# v3_Painting_Machine_Schematic.net
KiCad netlist of a schematic drawn in EAGLE
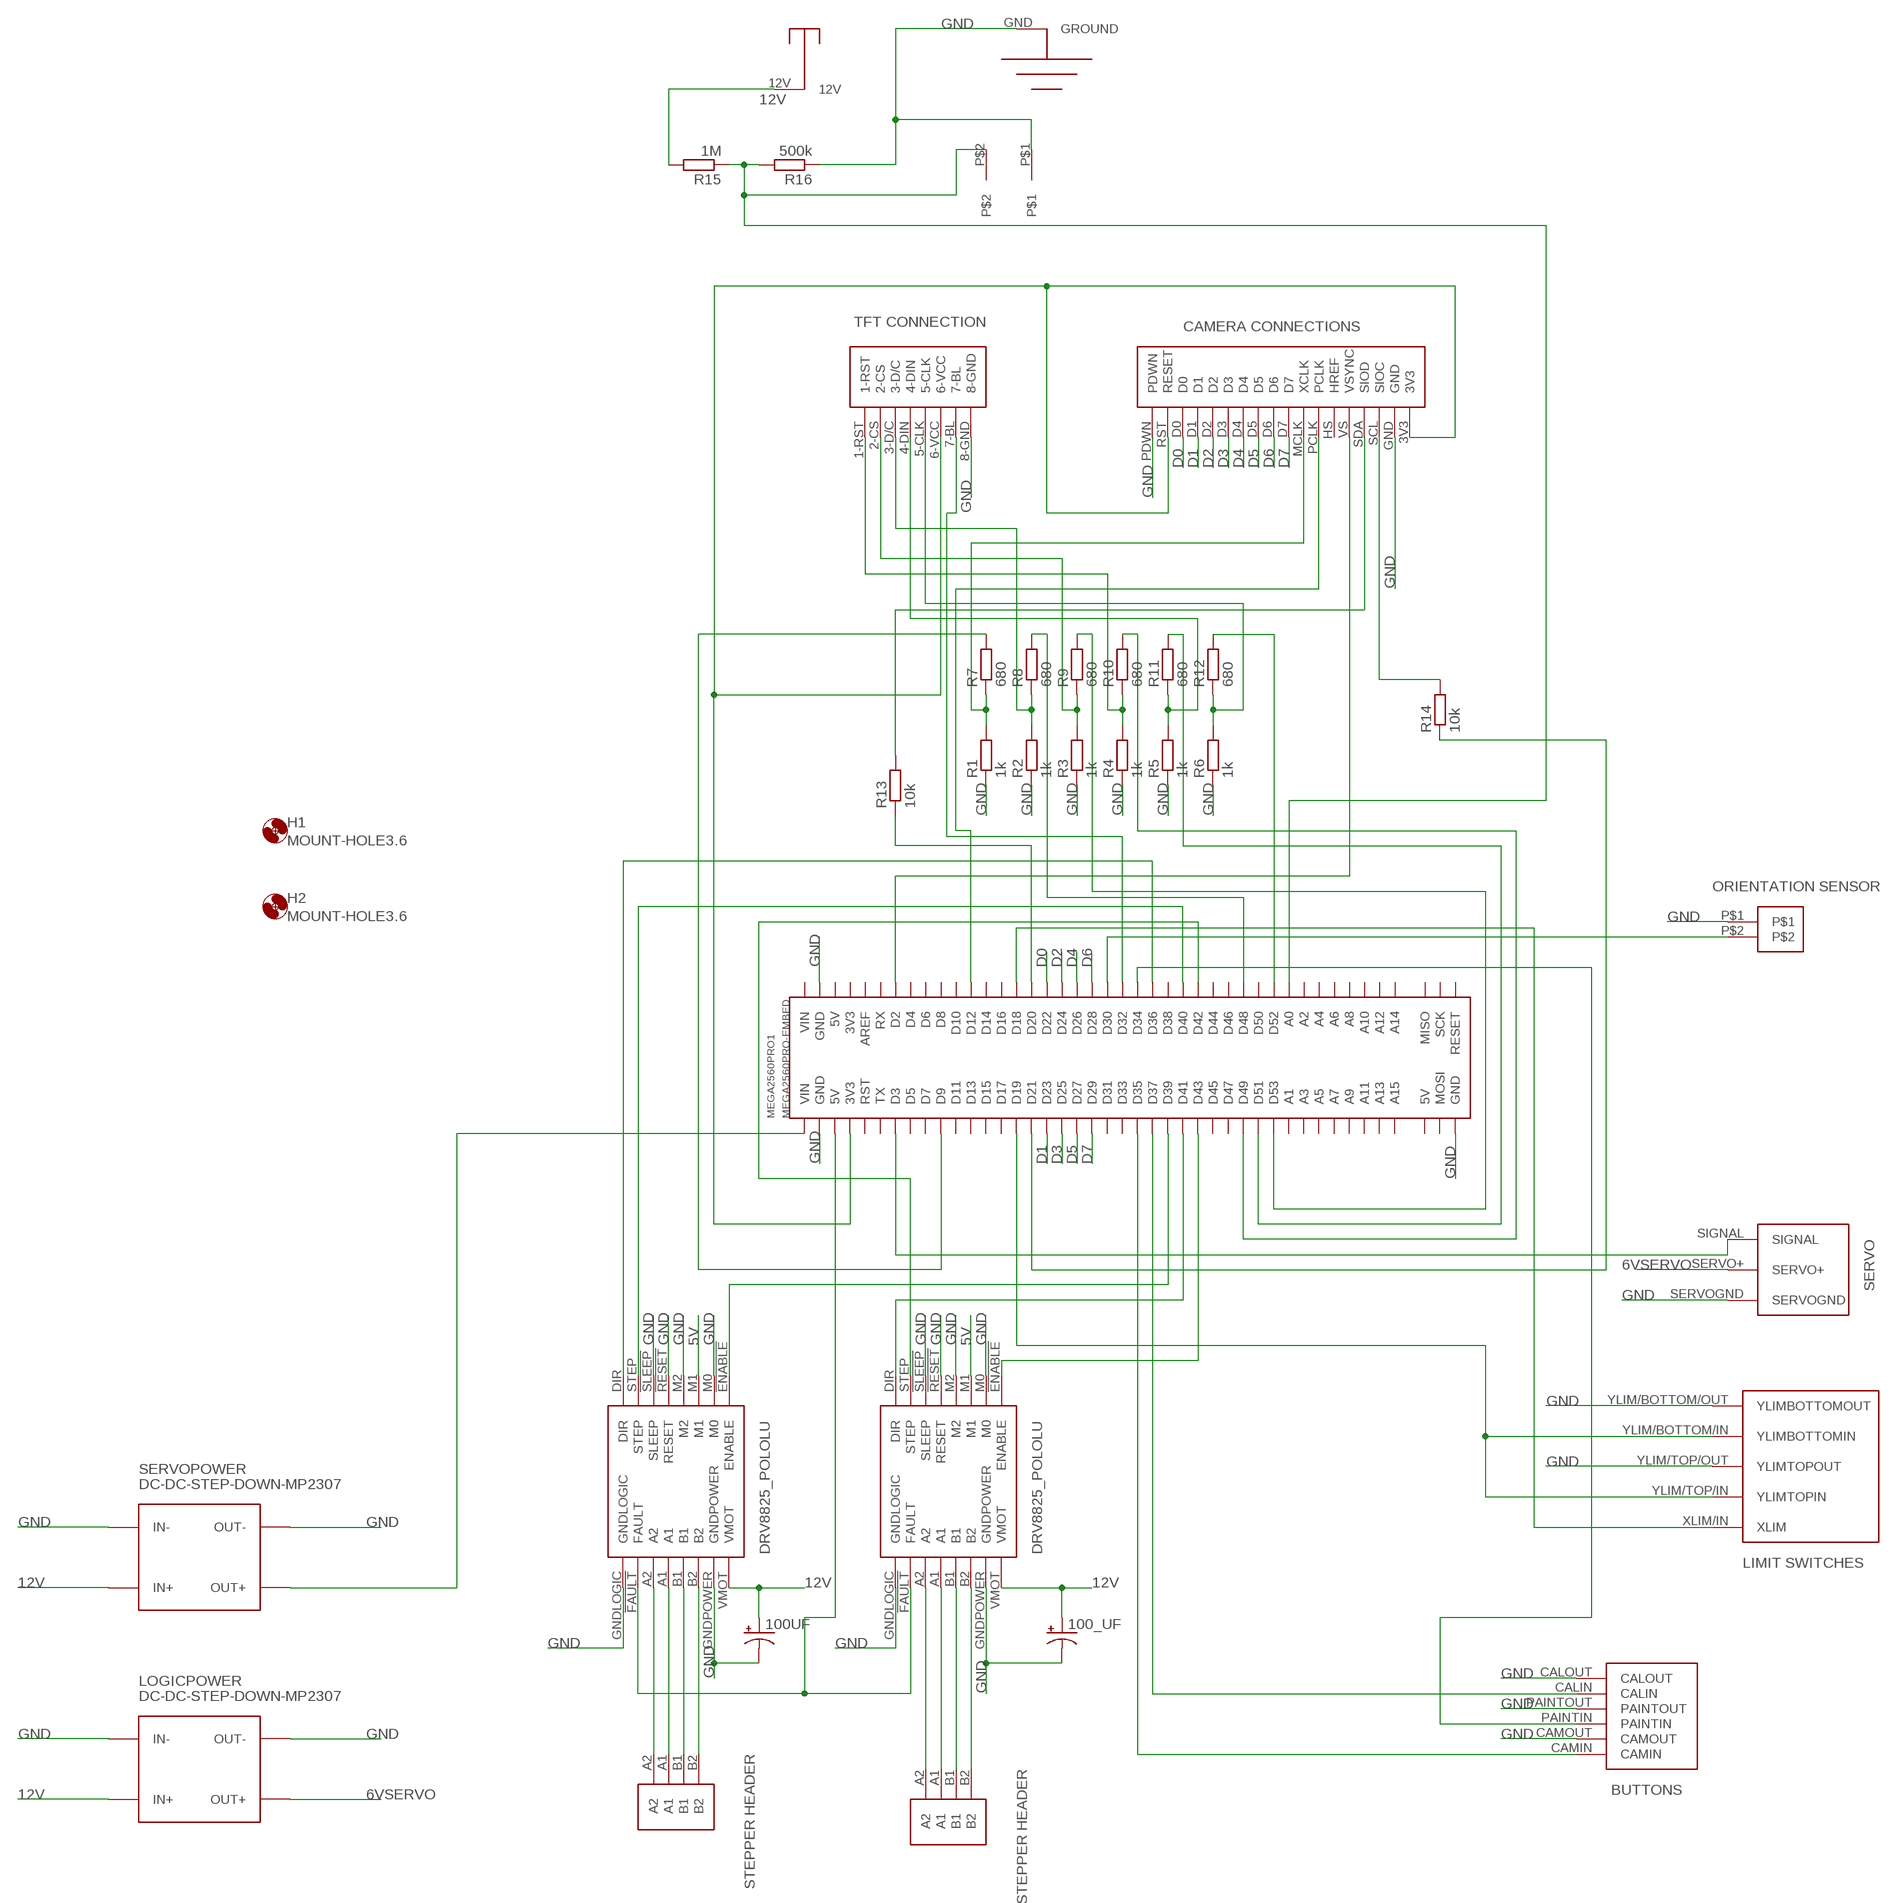
[diagram p0: schematic, sheet 1]

(export (version "E")
  (design (tool "Eeschema 10.0.6"))
  (components
    (comp (ref "100UF")
      (value "CPOL-USB45181B")
      (footprint "eagle-import:B45181B")
      (libsource (lib "eagle-import") (part "CPOL-USB45181B"))
    )
    (comp (ref "100_UF")
      (value "CPOL-USB45181B")
      (footprint "eagle-import:B45181B")
      (libsource (lib "eagle-import") (part "CPOL-USB45181B"))
    )
    (comp (ref "H1")
      (value "MOUNT-HOLE3.6")
      (footprint "eagle-import:3,6")
      (libsource (lib "eagle-import") (part "MOUNT-HOLE3.6"))
    )
    (comp (ref "H2")
      (value "MOUNT-HOLE3.6")
      (footprint "eagle-import:3,6")
      (libsource (lib "eagle-import") (part "MOUNT-HOLE3.6"))
    )
    (comp (ref "LOGICPOWER")
      (value "DC-DC-STEP-DOWN-MP2307")
      (footprint "eagle-import:DC-DC-STEP-DOWN-MP2307")
      (libsource (lib "eagle-import") (part "DC-DC-STEP-DOWN-MP2307"))
    )
    (comp (ref "MEGA2560PRO1")
      (value "MEGA2560PRO-EMBED")
      (footprint "eagle-import:MEGA2560PRO-EMBED")
      (libsource (lib "eagle-import") (part "MEGA2560PRO-EMBED"))
    )
    (comp (ref "R1")
      (value "1k")
      (footprint "eagle-import:0207_7")
      (libsource (lib "eagle-import") (part "R-EU_0207/7"))
    )
    (comp (ref "R2")
      (value "1k")
      (footprint "eagle-import:0207_7")
      (libsource (lib "eagle-import") (part "R-EU_0207/7"))
    )
    (comp (ref "R3")
      (value "1k")
      (footprint "eagle-import:0207_7")
      (libsource (lib "eagle-import") (part "R-EU_0207/7"))
    )
    (comp (ref "R4")
      (value "1k")
      (footprint "eagle-import:0207_7")
      (libsource (lib "eagle-import") (part "R-EU_0207/7"))
    )
    (comp (ref "R5")
      (value "1k")
      (footprint "eagle-import:0207_7")
      (libsource (lib "eagle-import") (part "R-EU_0207/7"))
    )
    (comp (ref "R6")
      (value "1k")
      (footprint "eagle-import:0207_7")
      (libsource (lib "eagle-import") (part "R-EU_0207/7"))
    )
    (comp (ref "R7")
      (value "680")
      (footprint "eagle-import:0207_7")
      (libsource (lib "eagle-import") (part "R-EU_0207/7"))
    )
    (comp (ref "R8")
      (value "680")
      (footprint "eagle-import:0207_7")
      (libsource (lib "eagle-import") (part "R-EU_0207/7"))
    )
    (comp (ref "R9")
      (value "680")
      (footprint "eagle-import:0207_7")
      (libsource (lib "eagle-import") (part "R-EU_0207/7"))
    )
    (comp (ref "R10")
      (value "680")
      (footprint "eagle-import:0207_7")
      (libsource (lib "eagle-import") (part "R-EU_0207/7"))
    )
    (comp (ref "R11")
      (value "680")
      (footprint "eagle-import:0207_7")
      (libsource (lib "eagle-import") (part "R-EU_0207/7"))
    )
    (comp (ref "R12")
      (value "680")
      (footprint "eagle-import:0207_7")
      (libsource (lib "eagle-import") (part "R-EU_0207/7"))
    )
    (comp (ref "R13")
      (value "10k")
      (footprint "eagle-import:0207_7")
      (libsource (lib "eagle-import") (part "R-EU_0207/7"))
    )
    (comp (ref "R14")
      (value "10k")
      (footprint "eagle-import:0207_7")
      (libsource (lib "eagle-import") (part "R-EU_0207/7"))
    )
    (comp (ref "R15")
      (value "1M")
      (footprint "eagle-import:0207_7")
      (libsource (lib "eagle-import") (part "R-EU_0207/7"))
    )
    (comp (ref "R16")
      (value "500k")
      (footprint "eagle-import:0207_7")
      (libsource (lib "eagle-import") (part "R-EU_0207/7"))
    )
    (comp (ref "SERVOPOWER")
      (value "DC-DC-STEP-DOWN-MP2307")
      (footprint "eagle-import:DC-DC-STEP-DOWN-MP2307")
      (libsource (lib "eagle-import") (part "DC-DC-STEP-DOWN-MP2307"))
    )
    (comp (ref "U$1")
      (value "DRV8825_POLOLU_CARRIER")
      (footprint "eagle-import:DRV8825_POLOLU")
      (libsource (lib "eagle-import") (part "DRV8825_POLOLU_CARRIER"))
    )
    (comp (ref "U$2")
      (value "DRV8825_POLOLU_CARRIER")
      (footprint "eagle-import:DRV8825_POLOLU")
      (libsource (lib "eagle-import") (part "DRV8825_POLOLU_CARRIER"))
    )
    (comp (ref "U$4")
      (value "TFT/CONNECTIONS")
      (footprint "eagle-import:TFTCONNECTIONS")
      (libsource (lib "eagle-import") (part "TFT/CONNECTIONS"))
    )
    (comp (ref "U$5")
      (value "OV7670CONNECTIONS")
      (footprint "eagle-import:CAMERACONNECTIONS")
      (libsource (lib "eagle-import") (part "OV7670CONNECTIONS"))
    )
    (comp (ref "U$6")
      (value "ORIENTATIONSENSOR")
      (footprint "eagle-import:ORIENTATIONSENSOR")
      (libsource (lib "eagle-import") (part "ORIENTATIONSENSOR"))
    )
    (comp (ref "U$7")
      (value "12V")
      (footprint "eagle-import:VCC")
      (libsource (lib "eagle-import") (part "12V"))
    )
    (comp (ref "U$8")
      (value "GROUND")
      (footprint "eagle-import:GROUND")
      (libsource (lib "eagle-import") (part "GROUND"))
    )
    (comp (ref "U$9")
      (value "STEPPER_HEADER")
      (footprint "eagle-import:STEPPER_HEADER")
      (libsource (lib "eagle-import") (part "STEPPER_HEADER"))
    )
    (comp (ref "U$10")
      (value "STEPPER_HEADER")
      (footprint "eagle-import:STEPPER_HEADER")
      (libsource (lib "eagle-import") (part "STEPPER_HEADER"))
    )
    (comp (ref "U$11")
      (value "SERVO")
      (footprint "eagle-import:SERVO")
      (libsource (lib "eagle-import") (part "SERVO"))
    )
    (comp (ref "U$12")
      (value "LIMITSWITCHES")
      (footprint "eagle-import:LIMITSWITCHES")
      (libsource (lib "eagle-import") (part "LIMITSWITCHES"))
    )
    (comp (ref "U$13")
      (value "BUTTONS")
      (footprint "eagle-import:INPUTBUTTONS")
      (libsource (lib "eagle-import") (part "BUTTONS"))
    )
    (comp (ref "U$14")
      (value "CERAMICCAPACITOR")
      (footprint "eagle-import:CERAMICCAPACITOR")
      (libsource (lib "eagle-import") (part "CERAMICCAPACITOR"))
    )
  )
  (nets
    (net (code "1") (name "/5V") (class "Default")
      (node (ref "U$1") (pin "M1") (pinfunction "M1_M1") (pintype "bidirectional"))
      (node (ref "U$2") (pin "M1") (pinfunction "M1_M1") (pintype "bidirectional"))
    )
    (net (code "2") (name "/6VSERVO") (class "Default")
      (node (ref "LOGICPOWER") (pin "OUT+") (pinfunction "OUT+_OUT+") (pintype "bidirectional"))
      (node (ref "U$11") (pin "SERVO+") (pinfunction "SERVO+_SERVO+") (pintype "bidirectional"))
    )
    (net (code "3") (name "/12V") (class "Default")
      (node (ref "100UF") (pin "+") (pinfunction "+_+") (pintype "passive"))
      (node (ref "100_UF") (pin "+") (pinfunction "+_+") (pintype "passive"))
      (node (ref "LOGICPOWER") (pin "IN+") (pinfunction "IN+_IN+") (pintype "bidirectional"))
      (node (ref "R15") (pin "2") (pinfunction "2_2") (pintype "passive"))
      (node (ref "SERVOPOWER") (pin "IN+") (pinfunction "IN+_IN+") (pintype "bidirectional"))
      (node (ref "U$1") (pin "VMOT") (pinfunction "VMOT_VMOT") (pintype "bidirectional"))
      (node (ref "U$2") (pin "VMOT") (pinfunction "VMOT_VMOT") (pintype "bidirectional"))
      (node (ref "U$7") (pin "12V") (pinfunction "12V_12V") (pintype "bidirectional"))
    )
    (net (code "4") (name "/D0") (class "Default")
      (node (ref "MEGA2560PRO1") (pin "D22") (pinfunction "D22_D22") (pintype "bidirectional"))
      (node (ref "U$5") (pin "D0") (pinfunction "D0_D0") (pintype "bidirectional"))
    )
    (net (code "5") (name "/D1") (class "Default")
      (node (ref "MEGA2560PRO1") (pin "D23") (pinfunction "D23_D23") (pintype "bidirectional"))
      (node (ref "U$5") (pin "D1") (pinfunction "D1_D1") (pintype "bidirectional"))
    )
    (net (code "6") (name "/D2") (class "Default")
      (node (ref "MEGA2560PRO1") (pin "D24") (pinfunction "D24_D24") (pintype "bidirectional"))
      (node (ref "U$5") (pin "D2") (pinfunction "D2_D2") (pintype "bidirectional"))
    )
    (net (code "7") (name "/D3") (class "Default")
      (node (ref "MEGA2560PRO1") (pin "D25") (pinfunction "D25_D25") (pintype "bidirectional"))
      (node (ref "U$5") (pin "D3") (pinfunction "D3_D3") (pintype "bidirectional"))
    )
    (net (code "8") (name "/D4") (class "Default")
      (node (ref "MEGA2560PRO1") (pin "D26") (pinfunction "D26_D26") (pintype "bidirectional"))
      (node (ref "U$5") (pin "D4") (pinfunction "D4_D4") (pintype "bidirectional"))
    )
    (net (code "9") (name "/D5") (class "Default")
      (node (ref "MEGA2560PRO1") (pin "D27") (pinfunction "D27_D27") (pintype "bidirectional"))
      (node (ref "U$5") (pin "D5") (pinfunction "D5_D5") (pintype "bidirectional"))
    )
    (net (code "10") (name "/D6") (class "Default")
      (node (ref "MEGA2560PRO1") (pin "D28") (pinfunction "D28_D28") (pintype "bidirectional"))
      (node (ref "U$5") (pin "D6") (pinfunction "D6_D6") (pintype "bidirectional"))
    )
    (net (code "11") (name "/D7") (class "Default")
      (node (ref "MEGA2560PRO1") (pin "D29") (pinfunction "D29_D29") (pintype "bidirectional"))
      (node (ref "U$5") (pin "D7") (pinfunction "D7_D7") (pintype "bidirectional"))
    )
    (net (code "12") (name "/GND") (class "Default")
      (node (ref "100UF") (pin "-") (pinfunction "-_-") (pintype "passive"))
      (node (ref "100_UF") (pin "-") (pinfunction "-_-") (pintype "passive"))
      (node (ref "LOGICPOWER") (pin "IN-") (pinfunction "IN-_IN-") (pintype "bidirectional"))
      (node (ref "LOGICPOWER") (pin "OUT-") (pinfunction "OUT-_OUT-") (pintype "bidirectional"))
      (node (ref "MEGA2560PRO1") (pin "GND@1") (pinfunction "GND_GND@1") (pintype "bidirectional"))
      (node (ref "MEGA2560PRO1") (pin "GND@2") (pinfunction "GND_GND@2") (pintype "bidirectional"))
      (node (ref "MEGA2560PRO1") (pin "GND@3") (pinfunction "GND_GND@3") (pintype "bidirectional"))
      (node (ref "R1") (pin "1") (pinfunction "1_1") (pintype "passive"))
      (node (ref "R16") (pin "1") (pinfunction "1_1") (pintype "passive"))
      (node (ref "R2") (pin "1") (pinfunction "1_1") (pintype "passive"))
      (node (ref "R3") (pin "1") (pinfunction "1_1") (pintype "passive"))
      (node (ref "R4") (pin "1") (pinfunction "1_1") (pintype "passive"))
      (node (ref "R5") (pin "1") (pinfunction "1_1") (pintype "passive"))
      (node (ref "R6") (pin "1") (pinfunction "1_1") (pintype "passive"))
      (node (ref "SERVOPOWER") (pin "IN-") (pinfunction "IN-_IN-") (pintype "bidirectional"))
      (node (ref "SERVOPOWER") (pin "OUT-") (pinfunction "OUT-_OUT-") (pintype "bidirectional"))
      (node (ref "U$1") (pin "!RESET") (pinfunction "RESET_!RESET") (pintype "bidirectional"))
      (node (ref "U$1") (pin "!SLEEP") (pinfunction "SLEEP_!SLEEP") (pintype "bidirectional"))
      (node (ref "U$1") (pin "GNDLOGIC") (pinfunction "GNDLOGIC_GNDLOGIC") (pintype "bidirectional"))
      (node (ref "U$1") (pin "GNDPOWER") (pinfunction "GNDPOWER_GNDPOWER") (pintype "bidirectional"))
      (node (ref "U$1") (pin "M0") (pinfunction "M0_M0") (pintype "bidirectional"))
      (node (ref "U$1") (pin "M2") (pinfunction "M2_M2") (pintype "bidirectional"))
      (node (ref "U$11") (pin "SERVOGND") (pinfunction "SERVOGND_SERVOGND") (pintype "bidirectional"))
      (node (ref "U$12") (pin "YLIM/BOTTOM/OUT") (pinfunction "YLIMBOTTOMOUT_YLIM/BOTTOM/OUT") (pintype "bidirectional"))
      (node (ref "U$12") (pin "YLIM/TOP/OUT") (pinfunction "YLIMTOPOUT_YLIM/TOP/OUT") (pintype "bidirectional"))
      (node (ref "U$13") (pin "CALOUT") (pinfunction "CALOUT_CALOUT") (pintype "bidirectional"))
      (node (ref "U$13") (pin "CAMOUT") (pinfunction "CAMOUT_CAMOUT") (pintype "bidirectional"))
      (node (ref "U$13") (pin "PAINTOUT") (pinfunction "PAINTOUT_PAINTOUT") (pintype "bidirectional"))
      (node (ref "U$14") (pin "P$1") (pinfunction "P$1_P$1") (pintype "bidirectional"))
      (node (ref "U$2") (pin "!RESET") (pinfunction "RESET_!RESET") (pintype "bidirectional"))
      (node (ref "U$2") (pin "!SLEEP") (pinfunction "SLEEP_!SLEEP") (pintype "bidirectional"))
      (node (ref "U$2") (pin "GNDLOGIC") (pinfunction "GNDLOGIC_GNDLOGIC") (pintype "bidirectional"))
      (node (ref "U$2") (pin "GNDPOWER") (pinfunction "GNDPOWER_GNDPOWER") (pintype "bidirectional"))
      (node (ref "U$2") (pin "M0") (pinfunction "M0_M0") (pintype "bidirectional"))
      (node (ref "U$2") (pin "M2") (pinfunction "M2_M2") (pintype "bidirectional"))
      (node (ref "U$4") (pin "8-GND") (pinfunction "8-GND_8-GND") (pintype "bidirectional"))
      (node (ref "U$5") (pin "GND") (pinfunction "GND_GND") (pintype "bidirectional"))
      (node (ref "U$5") (pin "PDWN") (pinfunction "PDWN_PDWN") (pintype "bidirectional"))
      (node (ref "U$6") (pin "P$1") (pinfunction "P$1_P$1") (pintype "bidirectional"))
      (node (ref "U$8") (pin "GND") (pinfunction "GROUND_GND") (pintype "bidirectional"))
    )
    (net (code "13") (name "Net-(MEGA2560PRO1-PadA0)") (class "Default")
      (node (ref "MEGA2560PRO1") (pin "A0") (pinfunction "A0_A0") (pintype "bidirectional"))
      (node (ref "R15") (pin "1") (pinfunction "1_1") (pintype "passive"))
      (node (ref "R16") (pin "2") (pinfunction "2_2") (pintype "passive"))
      (node (ref "U$14") (pin "P$2") (pinfunction "P$2_P$2") (pintype "bidirectional"))
    )
    (net (code "14") (name "Net-(MEGA2560PRO1-PadD3)") (class "Default")
      (node (ref "MEGA2560PRO1") (pin "D3") (pinfunction "D3_D3") (pintype "bidirectional"))
      (node (ref "U$11") (pin "SIGNAL") (pinfunction "SIGNAL_SIGNAL") (pintype "bidirectional"))
    )
    (net (code "15") (name "Net-(MEGA2560PRO1-PadD9)") (class "Default")
      (node (ref "MEGA2560PRO1") (pin "D9") (pinfunction "D9_D9") (pintype "bidirectional"))
      (node (ref "R7") (pin "2") (pinfunction "2_2") (pintype "passive"))
    )
    (net (code "16") (name "Net-(MEGA2560PRO1-PadD12)") (class "Default")
      (node (ref "MEGA2560PRO1") (pin "D12") (pinfunction "D12_D12") (pintype "bidirectional"))
      (node (ref "U$5") (pin "PCLK") (pinfunction "PCLK_PCLK") (pintype "bidirectional"))
    )
    (net (code "17") (name "Net-(MEGA2560PRO1-PadD20)") (class "Default")
      (node (ref "MEGA2560PRO1") (pin "D20") (pinfunction "D20_D20") (pintype "bidirectional"))
      (node (ref "R13") (pin "1") (pinfunction "1_1") (pintype "passive"))
    )
    (net (code "18") (name "Net-(MEGA2560PRO1-PadD21)") (class "Default")
      (node (ref "MEGA2560PRO1") (pin "D21") (pinfunction "D21_D21") (pintype "bidirectional"))
      (node (ref "R14") (pin "1") (pinfunction "1_1") (pintype "passive"))
    )
    (net (code "19") (name "Net-(MEGA2560PRO1-PadD30)") (class "Default")
      (node (ref "MEGA2560PRO1") (pin "D30") (pinfunction "D30_D30") (pintype "bidirectional"))
      (node (ref "U$6") (pin "P$2") (pinfunction "P$2_P$2") (pintype "bidirectional"))
    )
    (net (code "20") (name "Net-(MEGA2560PRO1-PadD32)") (class "Default")
      (node (ref "MEGA2560PRO1") (pin "D32") (pinfunction "D32_D32") (pintype "bidirectional"))
      (node (ref "U$4") (pin "7-BL") (pinfunction "7-BL_7-BL") (pintype "bidirectional"))
    )
    (net (code "21") (name "Net-(MEGA2560PRO1-PadD34)") (class "Default")
      (node (ref "MEGA2560PRO1") (pin "D34") (pinfunction "D34_D34") (pintype "bidirectional"))
      (node (ref "U$13") (pin "PAINTIN") (pinfunction "PAINTIN_PAINTIN") (pintype "bidirectional"))
    )
    (net (code "22") (name "Net-(MEGA2560PRO1-PadD35)") (class "Default")
      (node (ref "MEGA2560PRO1") (pin "D35") (pinfunction "D35_D35") (pintype "bidirectional"))
      (node (ref "U$13") (pin "CAMIN") (pinfunction "CAMIN_CAMIN") (pintype "bidirectional"))
    )
    (net (code "23") (name "Net-(MEGA2560PRO1-PadD36)") (class "Default")
      (node (ref "MEGA2560PRO1") (pin "D36") (pinfunction "D36_D36") (pintype "bidirectional"))
      (node (ref "U$2") (pin "DIR") (pinfunction "DIR_DIR") (pintype "bidirectional"))
    )
    (net (code "24") (name "Net-(MEGA2560PRO1-PadD37)") (class "Default")
      (node (ref "MEGA2560PRO1") (pin "D37") (pinfunction "D37_D37") (pintype "bidirectional"))
      (node (ref "U$13") (pin "CALIN") (pinfunction "CALIN_CALIN") (pintype "bidirectional"))
    )
    (net (code "25") (name "Net-(MEGA2560PRO1-PadD40)") (class "Default")
      (node (ref "MEGA2560PRO1") (pin "D40") (pinfunction "D40_D40") (pintype "bidirectional"))
      (node (ref "U$2") (pin "STEP") (pinfunction "STEP_STEP") (pintype "bidirectional"))
    )
    (net (code "26") (name "Net-(MEGA2560PRO1-PadD41)") (class "Default")
      (node (ref "MEGA2560PRO1") (pin "D41") (pinfunction "D41_D41") (pintype "bidirectional"))
      (node (ref "U$1") (pin "DIR") (pinfunction "DIR_DIR") (pintype "bidirectional"))
    )
    (net (code "27") (name "Net-(MEGA2560PRO1-PadD42)") (class "Default")
      (node (ref "MEGA2560PRO1") (pin "D42") (pinfunction "D42_D42") (pintype "bidirectional"))
      (node (ref "U$1") (pin "STEP") (pinfunction "STEP_STEP") (pintype "bidirectional"))
    )
    (net (code "28") (name "Net-(MEGA2560PRO1-PadD48)") (class "Default")
      (node (ref "MEGA2560PRO1") (pin "D48") (pinfunction "D48_D48") (pintype "bidirectional"))
      (node (ref "R8") (pin "2") (pinfunction "2_2") (pintype "passive"))
    )
    (net (code "29") (name "Net-(MEGA2560PRO1-PadD49)") (class "Default")
      (node (ref "MEGA2560PRO1") (pin "D49") (pinfunction "D49_D49") (pintype "bidirectional"))
      (node (ref "R10") (pin "2") (pinfunction "2_2") (pintype "passive"))
    )
    (net (code "30") (name "Net-(MEGA2560PRO1-PadD51)") (class "Default")
      (node (ref "MEGA2560PRO1") (pin "D51") (pinfunction "D51_D51") (pintype "bidirectional"))
      (node (ref "R11") (pin "2") (pinfunction "2_2") (pintype "passive"))
    )
    (net (code "31") (name "Net-(MEGA2560PRO1-PadD52)") (class "Default")
      (node (ref "MEGA2560PRO1") (pin "D52") (pinfunction "D52_D52") (pintype "bidirectional"))
      (node (ref "R12") (pin "2") (pinfunction "2_2") (pintype "passive"))
    )
    (net (code "32") (name "Net-(MEGA2560PRO1-PadD53)") (class "Default")
      (node (ref "MEGA2560PRO1") (pin "D53") (pinfunction "D53_D53") (pintype "bidirectional"))
      (node (ref "R9") (pin "2") (pinfunction "2_2") (pintype "passive"))
    )
    (net (code "33") (name "Net-(MEGA2560PRO1-VIN-PadVIN@1)") (class "Default")
      (node (ref "MEGA2560PRO1") (pin "VIN@1") (pinfunction "VIN_VIN@1") (pintype "bidirectional"))
      (node (ref "SERVOPOWER") (pin "OUT+") (pinfunction "OUT+_OUT+") (pintype "bidirectional"))
    )
    (net (code "34") (name "Net-(R2-Pad2)") (class "Default")
      (node (ref "R2") (pin "2") (pinfunction "2_2") (pintype "passive"))
      (node (ref "R8") (pin "1") (pinfunction "1_1") (pintype "passive"))
      (node (ref "U$4") (pin "3-D/C") (pinfunction "3-D/C_3-D/C") (pintype "bidirectional"))
    )
    (net (code "35") (name "Net-(R3-Pad2)") (class "Default")
      (node (ref "R3") (pin "2") (pinfunction "2_2") (pintype "passive"))
      (node (ref "R9") (pin "1") (pinfunction "1_1") (pintype "passive"))
      (node (ref "U$4") (pin "2-CS") (pinfunction "2-CS_2-CS") (pintype "bidirectional"))
    )
    (net (code "36") (name "Net-(R10-Pad1)") (class "Default")
      (node (ref "R10") (pin "1") (pinfunction "1_1") (pintype "passive"))
      (node (ref "R4") (pin "2") (pinfunction "2_2") (pintype "passive"))
      (node (ref "U$4") (pin "1-RST") (pinfunction "1-RST_1-RST") (pintype "bidirectional"))
    )
    (net (code "37") (name "Net-(R11-Pad1)") (class "Default")
      (node (ref "R11") (pin "1") (pinfunction "1_1") (pintype "passive"))
      (node (ref "R5") (pin "2") (pinfunction "2_2") (pintype "passive"))
      (node (ref "U$4") (pin "4-DIN") (pinfunction "4-DIN_4-DIN") (pintype "bidirectional"))
    )
    (net (code "38") (name "Net-(R12-Pad1)") (class "Default")
      (node (ref "R12") (pin "1") (pinfunction "1_1") (pintype "passive"))
      (node (ref "R6") (pin "2") (pinfunction "2_2") (pintype "passive"))
      (node (ref "U$4") (pin "5-CLK") (pinfunction "5-CLK_5-CLK") (pintype "bidirectional"))
    )
    (net (code "39") (name "Net-(U$1-ENABLE)") (class "Default")
      (node (ref "MEGA2560PRO1") (pin "D43") (pinfunction "D43_D43") (pintype "bidirectional"))
      (node (ref "U$1") (pin "!ENABLE") (pinfunction "ENABLE_!ENABLE") (pintype "bidirectional"))
    )
    (net (code "40") (name "Net-(U$1-FAULT)") (class "Default")
      (node (ref "MEGA2560PRO1") (pin "5V@1") (pinfunction "5V_5V@1") (pintype "bidirectional"))
      (node (ref "U$1") (pin "!FAULT") (pinfunction "FAULT_!FAULT") (pintype "bidirectional"))
      (node (ref "U$2") (pin "!FAULT") (pinfunction "FAULT_!FAULT") (pintype "bidirectional"))
    )
    (net (code "41") (name "Net-(U$1-PadA1)") (class "Default")
      (node (ref "U$1") (pin "A1") (pinfunction "A1_A1") (pintype "bidirectional"))
      (node (ref "U$10") (pin "A1") (pinfunction "A1_A1") (pintype "bidirectional"))
    )
    (net (code "42") (name "Net-(U$1-PadA2)") (class "Default")
      (node (ref "U$1") (pin "A2") (pinfunction "A2_A2") (pintype "bidirectional"))
      (node (ref "U$10") (pin "A2") (pinfunction "A2_A2") (pintype "bidirectional"))
    )
    (net (code "43") (name "Net-(U$1-PadB1)") (class "Default")
      (node (ref "U$1") (pin "B1") (pinfunction "B1_B1") (pintype "bidirectional"))
      (node (ref "U$10") (pin "B1") (pinfunction "B1_B1") (pintype "bidirectional"))
    )
    (net (code "44") (name "Net-(U$1-PadB2)") (class "Default")
      (node (ref "U$1") (pin "B2") (pinfunction "B2_B2") (pintype "bidirectional"))
      (node (ref "U$10") (pin "B2") (pinfunction "B2_B2") (pintype "bidirectional"))
    )
    (net (code "45") (name "Net-(U$2-ENABLE)") (class "Default")
      (node (ref "MEGA2560PRO1") (pin "D39") (pinfunction "D39_D39") (pintype "bidirectional"))
      (node (ref "U$2") (pin "!ENABLE") (pinfunction "ENABLE_!ENABLE") (pintype "bidirectional"))
    )
    (net (code "46") (name "Net-(U$2-PadA1)") (class "Default")
      (node (ref "U$2") (pin "A1") (pinfunction "A1_A1") (pintype "bidirectional"))
      (node (ref "U$9") (pin "A1") (pinfunction "A1_A1") (pintype "bidirectional"))
    )
    (net (code "47") (name "Net-(U$2-PadA2)") (class "Default")
      (node (ref "U$2") (pin "A2") (pinfunction "A2_A2") (pintype "bidirectional"))
      (node (ref "U$9") (pin "A2") (pinfunction "A2_A2") (pintype "bidirectional"))
    )
    (net (code "48") (name "Net-(U$2-PadB1)") (class "Default")
      (node (ref "U$2") (pin "B1") (pinfunction "B1_B1") (pintype "bidirectional"))
      (node (ref "U$9") (pin "B1") (pinfunction "B1_B1") (pintype "bidirectional"))
    )
    (net (code "49") (name "Net-(U$2-PadB2)") (class "Default")
      (node (ref "U$2") (pin "B2") (pinfunction "B2_B2") (pintype "bidirectional"))
      (node (ref "U$9") (pin "B2") (pinfunction "B2_B2") (pintype "bidirectional"))
    )
    (net (code "50") (name "Net-(U$5-RESET)") (class "Default")
      (node (ref "MEGA2560PRO1") (pin "3V3@1") (pinfunction "3V3_3V3@1") (pintype "bidirectional"))
      (node (ref "U$4") (pin "6-VCC") (pinfunction "6-VCC_6-VCC") (pintype "bidirectional"))
      (node (ref "U$5") (pin "3V3") (pinfunction "3V3_3V3") (pintype "bidirectional"))
      (node (ref "U$5") (pin "RST") (pinfunction "RESET_RST") (pintype "bidirectional"))
    )
    (net (code "51") (name "Net-(U$5-SIOC)") (class "Default")
      (node (ref "R14") (pin "2") (pinfunction "2_2") (pintype "passive"))
      (node (ref "U$5") (pin "SCL") (pinfunction "SIOC_SCL") (pintype "bidirectional"))
    )
    (net (code "52") (name "Net-(U$5-SIOD)") (class "Default")
      (node (ref "R13") (pin "2") (pinfunction "2_2") (pintype "passive"))
      (node (ref "U$5") (pin "SDA") (pinfunction "SIOD_SDA") (pintype "bidirectional"))
    )
    (net (code "53") (name "Net-(U$5-VSYNC)") (class "Default")
      (node (ref "MEGA2560PRO1") (pin "D2") (pinfunction "D2_D2") (pintype "bidirectional"))
      (node (ref "U$5") (pin "VS") (pinfunction "VSYNC_VS") (pintype "bidirectional"))
    )
    (net (code "54") (name "Net-(U$5-XCLK)") (class "Default")
      (node (ref "R1") (pin "2") (pinfunction "2_2") (pintype "passive"))
      (node (ref "R7") (pin "1") (pinfunction "1_1") (pintype "passive"))
      (node (ref "U$5") (pin "MCLK") (pinfunction "XCLK_MCLK") (pintype "bidirectional"))
    )
    (net (code "55") (name "Net-(U$12-XLIM)") (class "Default")
      (node (ref "MEGA2560PRO1") (pin "D18") (pinfunction "D18_D18") (pintype "bidirectional"))
      (node (ref "U$12") (pin "XLIM/IN") (pinfunction "XLIM_XLIM/IN") (pintype "bidirectional"))
    )
    (net (code "56") (name "Net-(U$12-YLIMBOTTOMIN)") (class "Default")
      (node (ref "MEGA2560PRO1") (pin "D19") (pinfunction "D19_D19") (pintype "bidirectional"))
      (node (ref "U$12") (pin "YLIM/BOTTOM/IN") (pinfunction "YLIMBOTTOMIN_YLIM/BOTTOM/IN") (pintype "bidirectional"))
      (node (ref "U$12") (pin "YLIM/TOP/IN") (pinfunction "YLIMTOPIN_YLIM/TOP/IN") (pintype "bidirectional"))
    )
    (net (code "57") (name "unconnected-(MEGA2560PRO1-3V3-Pad3V3@2)") (class "Default")
      (node (ref "MEGA2560PRO1") (pin "3V3@2") (pinfunction "3V3_3V3@2") (pintype "bidirectional"))
    )
    (net (code "58") (name "unconnected-(MEGA2560PRO1-5V-Pad5V@2)") (class "Default")
      (node (ref "MEGA2560PRO1") (pin "5V@2") (pinfunction "5V_5V@2") (pintype "bidirectional"))
    )
    (net (code "59") (name "unconnected-(MEGA2560PRO1-5V-Pad5V@3)") (class "Default")
      (node (ref "MEGA2560PRO1") (pin "5V@3") (pinfunction "5V_5V@3") (pintype "bidirectional"))
    )
    (net (code "60") (name "unconnected-(MEGA2560PRO1-PadA1)") (class "Default")
      (node (ref "MEGA2560PRO1") (pin "A1") (pinfunction "A1_A1") (pintype "bidirectional"))
    )
    (net (code "61") (name "unconnected-(MEGA2560PRO1-PadA2)") (class "Default")
      (node (ref "MEGA2560PRO1") (pin "A2") (pinfunction "A2_A2") (pintype "bidirectional"))
    )
    (net (code "62") (name "unconnected-(MEGA2560PRO1-PadA3)") (class "Default")
      (node (ref "MEGA2560PRO1") (pin "A3") (pinfunction "A3_A3") (pintype "bidirectional"))
    )
    (net (code "63") (name "unconnected-(MEGA2560PRO1-PadA4)") (class "Default")
      (node (ref "MEGA2560PRO1") (pin "A4") (pinfunction "A4_A4") (pintype "bidirectional"))
    )
    (net (code "64") (name "unconnected-(MEGA2560PRO1-PadA5)") (class "Default")
      (node (ref "MEGA2560PRO1") (pin "A5") (pinfunction "A5_A5") (pintype "bidirectional"))
    )
    (net (code "65") (name "unconnected-(MEGA2560PRO1-PadA6)") (class "Default")
      (node (ref "MEGA2560PRO1") (pin "A6") (pinfunction "A6_A6") (pintype "bidirectional"))
    )
    (net (code "66") (name "unconnected-(MEGA2560PRO1-PadA7)") (class "Default")
      (node (ref "MEGA2560PRO1") (pin "A7") (pinfunction "A7_A7") (pintype "bidirectional"))
    )
    (net (code "67") (name "unconnected-(MEGA2560PRO1-PadA8)") (class "Default")
      (node (ref "MEGA2560PRO1") (pin "A8") (pinfunction "A8_A8") (pintype "bidirectional"))
    )
    (net (code "68") (name "unconnected-(MEGA2560PRO1-PadA9)") (class "Default")
      (node (ref "MEGA2560PRO1") (pin "A9") (pinfunction "A9_A9") (pintype "bidirectional"))
    )
    (net (code "69") (name "unconnected-(MEGA2560PRO1-PadA10)") (class "Default")
      (node (ref "MEGA2560PRO1") (pin "A10") (pinfunction "A10_A10") (pintype "bidirectional"))
    )
    (net (code "70") (name "unconnected-(MEGA2560PRO1-PadA11)") (class "Default")
      (node (ref "MEGA2560PRO1") (pin "A11") (pinfunction "A11_A11") (pintype "bidirectional"))
    )
    (net (code "71") (name "unconnected-(MEGA2560PRO1-PadA12)") (class "Default")
      (node (ref "MEGA2560PRO1") (pin "A12") (pinfunction "A12_A12") (pintype "bidirectional"))
    )
    (net (code "72") (name "unconnected-(MEGA2560PRO1-PadA13)") (class "Default")
      (node (ref "MEGA2560PRO1") (pin "A13") (pinfunction "A13_A13") (pintype "bidirectional"))
    )
    (net (code "73") (name "unconnected-(MEGA2560PRO1-PadA14)") (class "Default")
      (node (ref "MEGA2560PRO1") (pin "A14") (pinfunction "A14_A14") (pintype "bidirectional"))
    )
    (net (code "74") (name "unconnected-(MEGA2560PRO1-PadA15)") (class "Default")
      (node (ref "MEGA2560PRO1") (pin "A15") (pinfunction "A15_A15") (pintype "bidirectional"))
    )
    (net (code "75") (name "unconnected-(MEGA2560PRO1-PadAREF)") (class "Default")
      (node (ref "MEGA2560PRO1") (pin "AREF") (pinfunction "AREF_AREF") (pintype "bidirectional"))
    )
    (net (code "76") (name "unconnected-(MEGA2560PRO1-PadD4)") (class "Default")
      (node (ref "MEGA2560PRO1") (pin "D4") (pinfunction "D4_D4") (pintype "bidirectional"))
    )
    (net (code "77") (name "unconnected-(MEGA2560PRO1-PadD5)") (class "Default")
      (node (ref "MEGA2560PRO1") (pin "D5") (pinfunction "D5_D5") (pintype "bidirectional"))
    )
    (net (code "78") (name "unconnected-(MEGA2560PRO1-PadD6)") (class "Default")
      (node (ref "MEGA2560PRO1") (pin "D6") (pinfunction "D6_D6") (pintype "bidirectional"))
    )
    (net (code "79") (name "unconnected-(MEGA2560PRO1-PadD7)") (class "Default")
      (node (ref "MEGA2560PRO1") (pin "D7") (pinfunction "D7_D7") (pintype "bidirectional"))
    )
    (net (code "80") (name "unconnected-(MEGA2560PRO1-PadD8)") (class "Default")
      (node (ref "MEGA2560PRO1") (pin "D8") (pinfunction "D8_D8") (pintype "bidirectional"))
    )
    (net (code "81") (name "unconnected-(MEGA2560PRO1-PadD10)") (class "Default")
      (node (ref "MEGA2560PRO1") (pin "D10") (pinfunction "D10_D10") (pintype "bidirectional"))
    )
    (net (code "82") (name "unconnected-(MEGA2560PRO1-PadD11)") (class "Default")
      (node (ref "MEGA2560PRO1") (pin "D11") (pinfunction "D11_D11") (pintype "bidirectional"))
    )
    (net (code "83") (name "unconnected-(MEGA2560PRO1-PadD13)") (class "Default")
      (node (ref "MEGA2560PRO1") (pin "D13") (pinfunction "D13_D13") (pintype "bidirectional"))
    )
    (net (code "84") (name "unconnected-(MEGA2560PRO1-PadD14)") (class "Default")
      (node (ref "MEGA2560PRO1") (pin "D14") (pinfunction "D14_D14") (pintype "bidirectional"))
    )
    (net (code "85") (name "unconnected-(MEGA2560PRO1-PadD15)") (class "Default")
      (node (ref "MEGA2560PRO1") (pin "D15") (pinfunction "D15_D15") (pintype "bidirectional"))
    )
    (net (code "86") (name "unconnected-(MEGA2560PRO1-PadD16)") (class "Default")
      (node (ref "MEGA2560PRO1") (pin "D16") (pinfunction "D16_D16") (pintype "bidirectional"))
    )
    (net (code "87") (name "unconnected-(MEGA2560PRO1-PadD17)") (class "Default")
      (node (ref "MEGA2560PRO1") (pin "D17") (pinfunction "D17_D17") (pintype "bidirectional"))
    )
    (net (code "88") (name "unconnected-(MEGA2560PRO1-PadD31)") (class "Default")
      (node (ref "MEGA2560PRO1") (pin "D31") (pinfunction "D31_D31") (pintype "bidirectional"))
    )
    (net (code "89") (name "unconnected-(MEGA2560PRO1-PadD33)") (class "Default")
      (node (ref "MEGA2560PRO1") (pin "D33") (pinfunction "D33_D33") (pintype "bidirectional"))
    )
    (net (code "90") (name "unconnected-(MEGA2560PRO1-PadD38)") (class "Default")
      (node (ref "MEGA2560PRO1") (pin "D38") (pinfunction "D38_D38") (pintype "bidirectional"))
    )
    (net (code "91") (name "unconnected-(MEGA2560PRO1-PadD44)") (class "Default")
      (node (ref "MEGA2560PRO1") (pin "D44") (pinfunction "D44_D44") (pintype "bidirectional"))
    )
    (net (code "92") (name "unconnected-(MEGA2560PRO1-PadD45)") (class "Default")
      (node (ref "MEGA2560PRO1") (pin "D45") (pinfunction "D45_D45") (pintype "bidirectional"))
    )
    (net (code "93") (name "unconnected-(MEGA2560PRO1-PadD46)") (class "Default")
      (node (ref "MEGA2560PRO1") (pin "D46") (pinfunction "D46_D46") (pintype "bidirectional"))
    )
    (net (code "94") (name "unconnected-(MEGA2560PRO1-PadD47)") (class "Default")
      (node (ref "MEGA2560PRO1") (pin "D47") (pinfunction "D47_D47") (pintype "bidirectional"))
    )
    (net (code "95") (name "unconnected-(MEGA2560PRO1-PadD50)") (class "Default")
      (node (ref "MEGA2560PRO1") (pin "D50") (pinfunction "D50_D50") (pintype "bidirectional"))
    )
    (net (code "96") (name "unconnected-(MEGA2560PRO1-PadMISO)") (class "Default")
      (node (ref "MEGA2560PRO1") (pin "MISO") (pinfunction "MISO_MISO") (pintype "bidirectional"))
    )
    (net (code "97") (name "unconnected-(MEGA2560PRO1-PadMOSI)") (class "Default")
      (node (ref "MEGA2560PRO1") (pin "MOSI") (pinfunction "MOSI_MOSI") (pintype "bidirectional"))
    )
    (net (code "98") (name "unconnected-(MEGA2560PRO1-PadRESET)") (class "Default")
      (node (ref "MEGA2560PRO1") (pin "RESET") (pinfunction "RESET_RESET") (pintype "bidirectional"))
    )
    (net (code "99") (name "unconnected-(MEGA2560PRO1-PadRST)") (class "Default")
      (node (ref "MEGA2560PRO1") (pin "RST") (pinfunction "RST_RST") (pintype "bidirectional"))
    )
    (net (code "100") (name "unconnected-(MEGA2560PRO1-PadRX)") (class "Default")
      (node (ref "MEGA2560PRO1") (pin "RX") (pinfunction "RX_RX") (pintype "bidirectional"))
    )
    (net (code "101") (name "unconnected-(MEGA2560PRO1-PadSCK)") (class "Default")
      (node (ref "MEGA2560PRO1") (pin "SCK") (pinfunction "SCK_SCK") (pintype "bidirectional"))
    )
    (net (code "102") (name "unconnected-(MEGA2560PRO1-PadTX)") (class "Default")
      (node (ref "MEGA2560PRO1") (pin "TX") (pinfunction "TX_TX") (pintype "bidirectional"))
    )
    (net (code "103") (name "unconnected-(MEGA2560PRO1-VIN-PadVIN@2)") (class "Default")
      (node (ref "MEGA2560PRO1") (pin "VIN@2") (pinfunction "VIN_VIN@2") (pintype "bidirectional"))
    )
    (net (code "104") (name "unconnected-(U$5-HREF-PadHS)") (class "Default")
      (node (ref "U$5") (pin "HS") (pinfunction "HREF_HS") (pintype "bidirectional"))
    )
  )
)
